# NE555.net
KiCad netlist of a schematic drawn in EAGLE
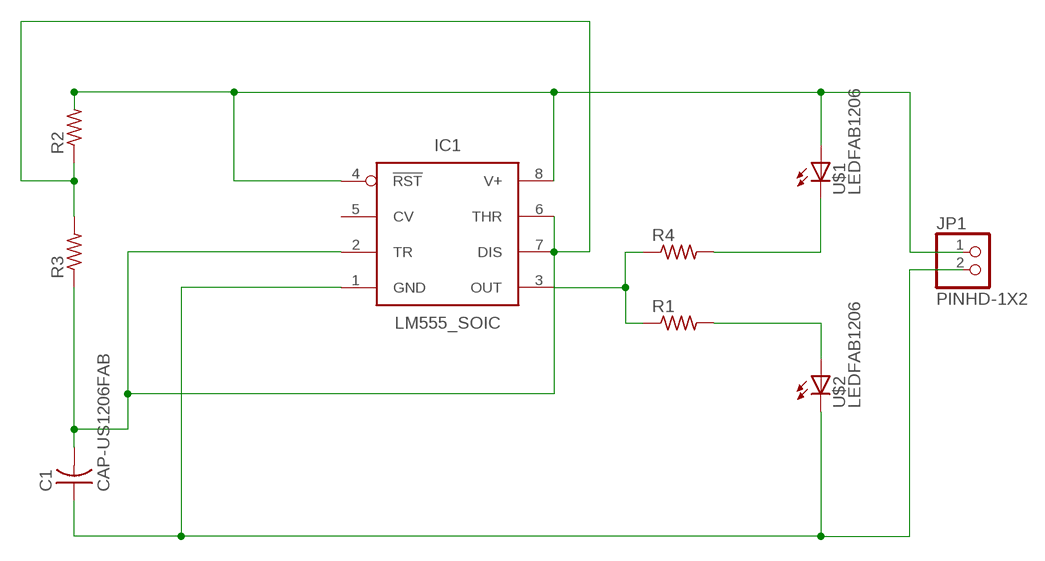
[diagram p0: schematic, sheet 1]

(export (version "E")
  (design (tool "Eeschema 10.0.6"))
  (components
    (comp (ref "C1")
      (value "CAP-US1206FAB")
      (footprint "eagle-import:C1206FAB")
      (libsource (lib "eagle-import") (part "CAP-US1206FAB"))
    )
    (comp (ref "IC1")
      (value "LM555_SOIC")
      (footprint "eagle-import:SOIC127P599X175-8N")
      (fields (field (name "MANUFACTURER") "Texas Instruments ") (field (name "MPN") "LM555CM/NOPB "))
      (libsource (lib "eagle-import") (part "555_SOICLM"))
    )
    (comp (ref "JP1")
      (value "PINHD-1X2")
      (footprint "eagle-import:1X02")
      (libsource (lib "eagle-import") (part "PINHD-1X2"))
    )
    (comp (ref "R1")
      (value "RES-US1206FAB")
      (footprint "eagle-import:R1206FAB")
      (libsource (lib "eagle-import") (part "RES-US1206FAB"))
    )
    (comp (ref "R2")
      (value "RES-US1206FAB")
      (footprint "eagle-import:R1206FAB")
      (libsource (lib "eagle-import") (part "RES-US1206FAB"))
    )
    (comp (ref "R3")
      (value "RES-US1206FAB")
      (footprint "eagle-import:R1206FAB")
      (libsource (lib "eagle-import") (part "RES-US1206FAB"))
    )
    (comp (ref "R4")
      (value "RES-US1206FAB")
      (footprint "eagle-import:R1206FAB")
      (libsource (lib "eagle-import") (part "RES-US1206FAB"))
    )
    (comp (ref "U$1")
      (value "LEDFAB1206")
      (footprint "eagle-import:LED1206FAB")
      (libsource (lib "eagle-import") (part "LEDFAB1206"))
    )
    (comp (ref "U$2")
      (value "LEDFAB1206")
      (footprint "eagle-import:LED1206FAB")
      (libsource (lib "eagle-import") (part "LEDFAB1206"))
    )
  )
  (nets
    (net (code "1") (name "Net-(IC1-DIS)") (class "Default")
      (node (ref "C1") (pin "2") (pinfunction "2_2") (pintype "passive"))
      (node (ref "IC1") (pin "2") (pinfunction "TR_2") (pintype "input"))
      (node (ref "IC1") (pin "6") (pinfunction "THR_6") (pintype "input"))
      (node (ref "IC1") (pin "7") (pinfunction "DIS_7") (pintype "input"))
      (node (ref "R2") (pin "1") (pinfunction "1_1") (pintype "passive"))
      (node (ref "R3") (pin "1") (pinfunction "1_1") (pintype "passive"))
      (node (ref "R3") (pin "2") (pinfunction "2_2") (pintype "passive"))
    )
    (net (code "2") (name "Net-(IC1-GND)") (class "Default")
      (node (ref "C1") (pin "1") (pinfunction "1_1") (pintype "passive"))
      (node (ref "IC1") (pin "1") (pinfunction "GND_1") (pintype "power_in"))
      (node (ref "JP1") (pin "2") (pinfunction "2_2") (pintype "passive"))
      (node (ref "U$2") (pin "2") (pinfunction "C_2") (pintype "passive"))
    )
    (net (code "3") (name "Net-(IC1-OUT)") (class "Default")
      (node (ref "IC1") (pin "3") (pinfunction "OUT_3") (pintype "output"))
      (node (ref "R1") (pin "1") (pinfunction "1_1") (pintype "passive"))
      (node (ref "R4") (pin "1") (pinfunction "1_1") (pintype "passive"))
    )
    (net (code "4") (name "Net-(IC1-V+)") (class "Default")
      (node (ref "IC1") (pin "4") (pinfunction "~{RST}_4") (pintype "input"))
      (node (ref "IC1") (pin "8") (pinfunction "V+_8") (pintype "power_in"))
      (node (ref "JP1") (pin "1") (pinfunction "1_1") (pintype "passive"))
      (node (ref "R2") (pin "2") (pinfunction "2_2") (pintype "passive"))
      (node (ref "U$1") (pin "1") (pinfunction "A_1") (pintype "passive"))
    )
    (net (code "5") (name "Net-(U$1-C)") (class "Default")
      (node (ref "R4") (pin "2") (pinfunction "2_2") (pintype "passive"))
      (node (ref "U$1") (pin "2") (pinfunction "C_2") (pintype "passive"))
    )
    (net (code "6") (name "Net-(U$2-A)") (class "Default")
      (node (ref "R1") (pin "2") (pinfunction "2_2") (pintype "passive"))
      (node (ref "U$2") (pin "1") (pinfunction "A_1") (pintype "passive"))
    )
    (net (code "7") (name "unconnected-(IC1-CV-Pad5)") (class "Default")
      (node (ref "IC1") (pin "5") (pinfunction "CV_5") (pintype "input"))
    )
  )
)
